# MCU.net
KiCad netlist of a schematic drawn in Altium Designer
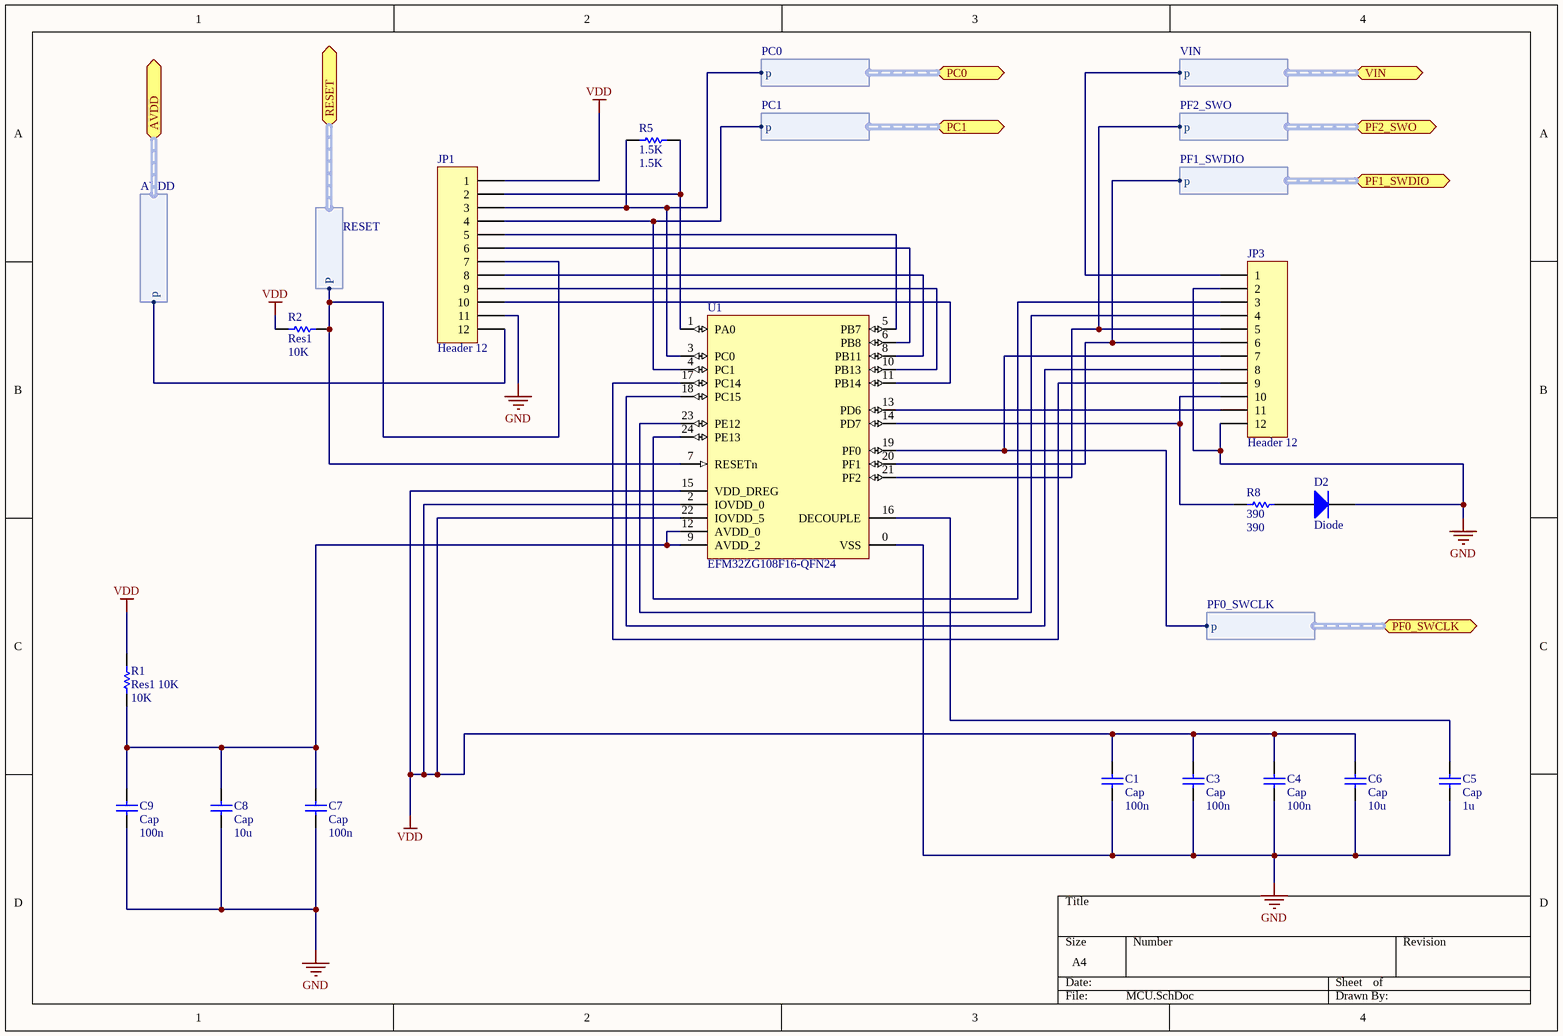
[diagram p0: MCU.SchDoc]

(export (version "E")
  (design (tool "Eeschema 10.0.6"))
  (components
    (comp (ref "C1")
      (value "Cap")
      (footprint "RAD-0.3")
      (description "Capacitor")
      (fields (field (name "ALTIUM_VALUE") "100n") (field (name "PUBLISHER") "Altium Limited"))
      (libsource (lib "Miscellaneous Devices") (part "Cap"))
    )
    (comp (ref "C3")
      (value "Cap")
      (footprint "RAD-0.3")
      (description "Capacitor")
      (fields (field (name "ALTIUM_VALUE") "100n") (field (name "PUBLISHER") "Altium Limited"))
      (libsource (lib "Miscellaneous Devices") (part "Cap"))
    )
    (comp (ref "C4")
      (value "Cap")
      (footprint "RAD-0.3")
      (description "Capacitor")
      (fields (field (name "ALTIUM_VALUE") "100n") (field (name "PUBLISHER") "Altium Limited"))
      (libsource (lib "Miscellaneous Devices") (part "Cap"))
    )
    (comp (ref "C5")
      (value "Cap")
      (footprint "RAD-0.3")
      (description "Capacitor")
      (fields (field (name "ALTIUM_VALUE") "1u") (field (name "PUBLISHER") "Altium Limited"))
      (libsource (lib "Miscellaneous Devices") (part "Cap"))
    )
    (comp (ref "C6")
      (value "Cap")
      (footprint "RAD-0.3")
      (description "Capacitor")
      (fields (field (name "ALTIUM_VALUE") "10u") (field (name "PUBLISHER") "Altium Limited"))
      (libsource (lib "Miscellaneous Devices") (part "Cap"))
    )
    (comp (ref "C7")
      (value "Cap")
      (footprint "RAD-0.3")
      (description "Capacitor")
      (fields (field (name "ALTIUM_VALUE") "100n") (field (name "PUBLISHER") "Altium Limited"))
      (libsource (lib "Miscellaneous Devices") (part "Cap"))
    )
    (comp (ref "C8")
      (value "Cap")
      (footprint "RAD-0.3")
      (description "Capacitor")
      (fields (field (name "ALTIUM_VALUE") "10u") (field (name "PUBLISHER") "Altium Limited"))
      (libsource (lib "Miscellaneous Devices") (part "Cap"))
    )
    (comp (ref "C9")
      (value "Cap")
      (footprint "RAD-0.3")
      (description "Capacitor")
      (fields (field (name "ALTIUM_VALUE") "100n") (field (name "PUBLISHER") "Altium Limited"))
      (libsource (lib "Miscellaneous Devices") (part "Cap"))
    )
    (comp (ref "D2")
      (value "Diode")
      (footprint "SMC")
      (description "Default Diode")
      (fields (field (name "PUBLISHER") "Altium Limited"))
      (libsource (lib "Miscellaneous Devices") (part "Diode"))
    )
    (comp (ref "JP1")
      (value "Header 12")
      (footprint "HDR1X12")
      (description "Header, 12-Pin")
      (fields (field (name "PUBLISHER") "Altium Limited"))
      (libsource (lib "Miscellaneous Connectors") (part "Header 12"))
    )
    (comp (ref "JP3")
      (value "Header 12")
      (footprint "HDR1X12")
      (description "Header, 12-Pin")
      (fields (field (name "PUBLISHER") "Altium Limited"))
      (libsource (lib "") (part "Header 12_1"))
    )
    (comp (ref "R1")
      (value "Res1 10K")
      (footprint "AXIAL-0.3")
      (description "Resistor")
      (fields (field (name "ALTIUM_VALUE") "10K") (field (name "PUBLISHER") "Altium Limited"))
      (libsource (lib "Miscellaneous Devices") (part "Res1"))
    )
    (comp (ref "R2")
      (value "Res1")
      (footprint "AXIAL-0.3")
      (description "Resistor")
      (fields (field (name "ALTIUM_VALUE") "10K") (field (name "PUBLISHER") "Altium Limited"))
      (libsource (lib "Miscellaneous Devices") (part "Res1"))
    )
    (comp (ref "R5")
      (value "1.5K")
      (footprint "AXIAL-0.3")
      (description "Resistor")
      (fields (field (name "ALTIUM_VALUE") "1.5K") (field (name "PUBLISHER") "Altium Limited"))
      (libsource (lib "Miscellaneous Devices") (part "Res1"))
    )
    (comp (ref "R8")
      (value "390")
      (footprint "AXIAL-0.3")
      (description "Resistor")
      (fields (field (name "ALTIUM_VALUE") "390") (field (name "PUBLISHER") "Altium Limited"))
      (libsource (lib "Miscellaneous Devices") (part "Res1"))
    )
    (comp (ref "U1")
      (value "EFM32ZG108F16-QFN24")
      (footprint "ENMR-QFN24_M")
      (fields (field (name "GENERIC PART NUMBER") "EFM32ZG108"))
      (libsource (lib "Altium Content Vault") (part "CMP-0270-00117-1"))
    )
  )
  (nets
    (net (code "15") (name "/{RESET}") (class "Default")
      (node (ref "JP1") (pin "7") (pinfunction "7_7") (pintype "passive"))
      (node (ref "R2") (pin "1") (pinfunction "1_1") (pintype "passive"))
      (node (ref "U1") (pin "7") (pinfunction "RESETn_7") (pintype "input"))
    )
    (net (code "17") (name "GND") (class "Default")
      (node (ref "C1") (pin "1") (pinfunction "1_1") (pintype "passive"))
      (node (ref "C3") (pin "1") (pinfunction "1_1") (pintype "passive"))
      (node (ref "C4") (pin "1") (pinfunction "1_1") (pintype "passive"))
      (node (ref "C5") (pin "1") (pinfunction "1_1") (pintype "passive"))
      (node (ref "C6") (pin "1") (pinfunction "1_1") (pintype "passive"))
      (node (ref "C7") (pin "1") (pinfunction "1_1") (pintype "passive"))
      (node (ref "C8") (pin "1") (pinfunction "1_1") (pintype "passive"))
      (node (ref "C9") (pin "1") (pinfunction "1_1") (pintype "passive"))
      (node (ref "D2") (pin "2") (pinfunction "K_2") (pintype "passive"))
      (node (ref "JP1") (pin "11") (pinfunction "11_11") (pintype "passive"))
      (node (ref "JP3") (pin "12") (pinfunction "12_12") (pintype "passive"))
      (node (ref "JP3") (pin "2") (pinfunction "2_2") (pintype "passive"))
      (node (ref "U1") (pin "0") (pinfunction "VSS_0") (pintype "power_in"))
    )
    (net (code "18") (name "Net-(D2-A)") (class "Default")
      (node (ref "D2") (pin "1") (pinfunction "A_1") (pintype "passive"))
      (node (ref "R8") (pin "2") (pinfunction "2_2") (pintype "passive"))
    )
    (net (code "19") (name "Net-(U1-AVDD_0)") (class "Default")
      (node (ref "C7") (pin "2") (pinfunction "2_2") (pintype "passive"))
      (node (ref "C8") (pin "2") (pinfunction "2_2") (pintype "passive"))
      (node (ref "C9") (pin "2") (pinfunction "2_2") (pintype "passive"))
      (node (ref "R1") (pin "1") (pinfunction "1_1") (pintype "passive"))
      (node (ref "U1") (pin "12") (pinfunction "AVDD_0_12") (pintype "power_in"))
      (node (ref "U1") (pin "9") (pinfunction "AVDD_2_9") (pintype "power_in"))
    )
    (net (code "20") (name "Net-(U1-DECOUPLE)") (class "Default")
      (node (ref "C5") (pin "2") (pinfunction "2_2") (pintype "passive"))
      (node (ref "U1") (pin "16") (pinfunction "DECOUPLE_16") (pintype "passive"))
    )
    (net (code "21") (name "Net-(U1-PA0)") (class "Default")
      (node (ref "JP1") (pin "2") (pinfunction "2_2") (pintype "passive"))
      (node (ref "R5") (pin "2") (pinfunction "2_2") (pintype "passive"))
      (node (ref "U1") (pin "1") (pinfunction "PA0_1") (pintype "bidirectional"))
    )
    (net (code "22") (name "Net-(U1-PB7)") (class "Default")
      (node (ref "JP1") (pin "5") (pinfunction "5_5") (pintype "passive"))
      (node (ref "U1") (pin "5") (pinfunction "PB7_5") (pintype "bidirectional"))
    )
    (net (code "23") (name "Net-(U1-PB8)") (class "Default")
      (node (ref "JP1") (pin "6") (pinfunction "6_6") (pintype "passive"))
      (node (ref "U1") (pin "6") (pinfunction "PB8_6") (pintype "bidirectional"))
    )
    (net (code "24") (name "Net-(U1-PB11)") (class "Default")
      (node (ref "JP1") (pin "8") (pinfunction "8_8") (pintype "passive"))
      (node (ref "U1") (pin "8") (pinfunction "PB11_8") (pintype "bidirectional"))
    )
    (net (code "25") (name "Net-(U1-PB13)") (class "Default")
      (node (ref "JP1") (pin "9") (pinfunction "9_9") (pintype "passive"))
      (node (ref "U1") (pin "10") (pinfunction "PB13_10") (pintype "bidirectional"))
    )
    (net (code "26") (name "Net-(U1-PB14)") (class "Default")
      (node (ref "JP1") (pin "10") (pinfunction "10_10") (pintype "passive"))
      (node (ref "U1") (pin "11") (pinfunction "PB14_11") (pintype "bidirectional"))
    )
    (net (code "27") (name "Net-(U1-PC0)") (class "Default")
      (node (ref "JP1") (pin "3") (pinfunction "3_3") (pintype "passive"))
      (node (ref "R5") (pin "1") (pinfunction "1_1") (pintype "passive"))
      (node (ref "U1") (pin "3") (pinfunction "PC0_3") (pintype "bidirectional"))
    )
    (net (code "28") (name "Net-(U1-PC1)") (class "Default")
      (node (ref "JP1") (pin "4") (pinfunction "4_4") (pintype "passive"))
      (node (ref "U1") (pin "4") (pinfunction "PC1_4") (pintype "bidirectional"))
    )
    (net (code "29") (name "Net-(U1-PC14)") (class "Default")
      (node (ref "JP3") (pin "9") (pinfunction "9_9") (pintype "passive"))
      (node (ref "U1") (pin "17") (pinfunction "PC14_17") (pintype "bidirectional"))
    )
    (net (code "30") (name "Net-(U1-PC15)") (class "Default")
      (node (ref "JP3") (pin "8") (pinfunction "8_8") (pintype "passive"))
      (node (ref "U1") (pin "18") (pinfunction "PC15_18") (pintype "bidirectional"))
    )
    (net (code "31") (name "Net-(U1-PD6)") (class "Default")
      (node (ref "JP3") (pin "11") (pinfunction "11_11") (pintype "passive"))
      (node (ref "U1") (pin "13") (pinfunction "PD6_13") (pintype "bidirectional"))
    )
    (net (code "32") (name "Net-(U1-PD7)") (class "Default")
      (node (ref "JP3") (pin "10") (pinfunction "10_10") (pintype "passive"))
      (node (ref "R8") (pin "1") (pinfunction "1_1") (pintype "passive"))
      (node (ref "U1") (pin "14") (pinfunction "PD7_14") (pintype "bidirectional"))
    )
    (net (code "33") (name "Net-(U1-PE12)") (class "Default")
      (node (ref "JP3") (pin "4") (pinfunction "4_4") (pintype "passive"))
      (node (ref "U1") (pin "23") (pinfunction "PE12_23") (pintype "bidirectional"))
    )
    (net (code "34") (name "Net-(U1-PE13)") (class "Default")
      (node (ref "JP3") (pin "3") (pinfunction "3_3") (pintype "passive"))
      (node (ref "U1") (pin "24") (pinfunction "PE13_24") (pintype "bidirectional"))
    )
    (net (code "35") (name "Net-(U1-PF0)") (class "Default")
      (node (ref "JP3") (pin "7") (pinfunction "7_7") (pintype "passive"))
      (node (ref "U1") (pin "19") (pinfunction "PF0_19") (pintype "bidirectional"))
    )
    (net (code "36") (name "Net-(U1-PF1)") (class "Default")
      (node (ref "JP3") (pin "6") (pinfunction "6_6") (pintype "passive"))
      (node (ref "U1") (pin "20") (pinfunction "PF1_20") (pintype "bidirectional"))
    )
    (net (code "37") (name "Net-(U1-PF2)") (class "Default")
      (node (ref "JP3") (pin "5") (pinfunction "5_5") (pintype "passive"))
      (node (ref "U1") (pin "21") (pinfunction "PF2_21") (pintype "bidirectional"))
    )
    (net (code "38") (name "VDD") (class "Default")
      (node (ref "C1") (pin "2") (pinfunction "2_2") (pintype "passive"))
      (node (ref "C3") (pin "2") (pinfunction "2_2") (pintype "passive"))
      (node (ref "C4") (pin "2") (pinfunction "2_2") (pintype "passive"))
      (node (ref "C6") (pin "2") (pinfunction "2_2") (pintype "passive"))
      (node (ref "JP1") (pin "1") (pinfunction "1_1") (pintype "passive"))
      (node (ref "R1") (pin "2") (pinfunction "2_2") (pintype "passive"))
      (node (ref "R2") (pin "2") (pinfunction "2_2") (pintype "passive"))
      (node (ref "U1") (pin "15") (pinfunction "VDD_DREG_15") (pintype "power_in"))
      (node (ref "U1") (pin "2") (pinfunction "IOVDD_0_2") (pintype "power_in"))
      (node (ref "U1") (pin "22") (pinfunction "IOVDD_5_22") (pintype "power_in"))
    )
    (net (code "39") (name "unconnected-(JP1-Pad12)") (class "Default")
      (node (ref "JP1") (pin "12") (pinfunction "12_12") (pintype "passive"))
    )
    (net (code "40") (name "unconnected-(JP3-Pad1)") (class "Default")
      (node (ref "JP3") (pin "1") (pinfunction "1_1") (pintype "passive"))
    )
  )
)
